# AudioOUT.net
KiCad netlist of a schematic drawn in Altium Designer
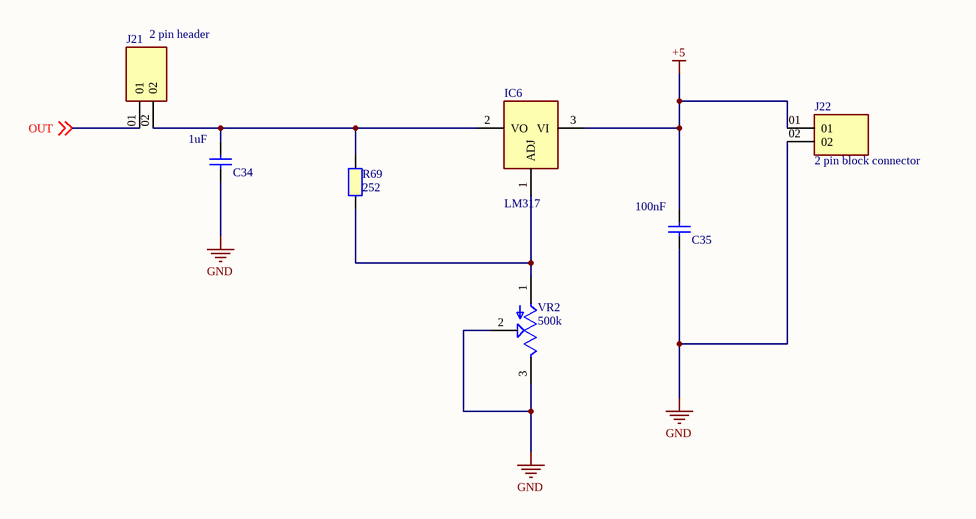
[diagram p0: AudioOUT.SchDoc]

(export (version "E")
  (design (tool "Eeschema 10.0.6"))
  (components
    (comp (ref "C34")
      (value "1uF")
      (footprint "CAPC2012X65N")
      (description "WCAP-CSGP Multilayer Ceramic Chip Capacitor, General Purpose, size 0201, NP0 Class I, 1uF, 25VDC")
      (fields
        (field (name "MANUFACTURER PART NUMBER") "885012004008")
        (field (name "MANUFACTURER") "Wurth Elektronik")
      )
      (libsource (lib "SpectrumComponents") (part "885012004008"))
    )
    (comp (ref "C35")
      (value "100nF")
      (footprint "CAPC2012X65N")
      (description "WCAP-CSGP Multilayer Ceramic Chip Capacitor, General Purpose, size 0201, NP0 Class I, 100nF, 25VDC")
      (fields
        (field (name "MANUFACTURER PART NUMBER") "885012004008")
        (field (name "MANUFACTURER") "Wurth Elektronik")
      )
      (libsource (lib "SpectrumComponents") (part "885012004008"))
    )
    (comp (ref "IC6")
      (value "LM317")
      (footprint "TO-220")
      (description "Standard Regulator Pos 1.2V to 37V 0.25A 3-Pin(3+Tab) TO-220 Tube")
      (fields (field (name "MF") "ON Semiconductor"))
      (libsource (lib "SpectrumComponents") (part "LM317"))
    )
    (comp (ref "J21")
      (value "2 pin header")
      (footprint "SpectrumComponents:SAMTEC_HTSW-102-07-TM-S")
      (description "2 pin header Jumper")
      (fields (field (name "MP") "HTSW10207TMS") (field (name "MF") "Samtec"))
      (libsource (lib "") (part "2 pin header_1"))
    )
    (comp (ref "J22")
      (value "2 pin block connector")
      (footprint "691210910002")
      (fields (field (name "MP") "HTSW10207TMS") (field (name "MF") "Samtec"))
      (libsource (lib "SpectrumComponents") (part "2 pin header"))
    )
    (comp (ref "R69")
      (value "252")
      (footprint "RESC2012X50N")
      (description "252 Resistor 0805")
      (fields (field (name "PART NUMBER") "TNPW080510K0BETA") (field (name "MANUFACTURER") "Vishay Dale"))
      (libsource (lib "SpectrumComponents") (part "RESISTOR 0805"))
    )
    (comp (ref "VR2")
      (value "500k")
      (footprint "TRIM_3362P-1-253LF")
      (description "25 kOhms 0.5W, 1/2W PC Pins Through Hole Trimmer Potentiometer Cermet 1 Turn Top Adjustment")
      (fields (field (name "MF") "Bourns") (field (name "MP") "3362P-1-253LF"))
      (libsource (lib "SpectrumComponents") (part "3362P-1-253LF"))
    )
  )
  (nets
    (net (code "1") (name "+5") (class "Default")
      (node (ref "C35") (pin "2") (pinfunction "2_2") (pintype "passive"))
      (node (ref "IC6") (pin "3") (pinfunction "VI_3") (pintype "power_in"))
      (node (ref "J22") (pin "01") (pinfunction "01_01") (pintype "passive"))
    )
    (net (code "2") (name "GND") (class "Default")
      (node (ref "C34") (pin "1") (pinfunction "1_1") (pintype "passive"))
      (node (ref "C35") (pin "1") (pinfunction "1_1") (pintype "passive"))
      (node (ref "J22") (pin "02") (pinfunction "02_02") (pintype "passive"))
      (node (ref "VR2") (pin "2") (pinfunction "WIPER_2") (pintype "passive"))
      (node (ref "VR2") (pin "3") (pinfunction "CW_3") (pintype "passive"))
    )
    (net (code "3") (name "Net-(IC6-ADJ)") (class "Default")
      (node (ref "IC6") (pin "1") (pinfunction "ADJ_1") (pintype "power_in"))
      (node (ref "R69") (pin "2") (pinfunction "2_2") (pintype "passive"))
      (node (ref "VR2") (pin "1") (pinfunction "CCW_1") (pintype "passive"))
    )
    (net (code "4") (name "Net-(IC6-VO)") (class "Default")
      (node (ref "C34") (pin "2") (pinfunction "2_2") (pintype "passive"))
      (node (ref "IC6") (pin "2") (pinfunction "VO_2") (pintype "power_in"))
      (node (ref "J21") (pin "02") (pinfunction "02_02") (pintype "passive"))
      (node (ref "R69") (pin "1") (pinfunction "1_1") (pintype "passive"))
    )
    (net (code "5") (name "OUT") (class "Default")
      (node (ref "J21") (pin "01") (pinfunction "01_01") (pintype "passive"))
    )
  )
)
